# INPUT.net
KiCad netlist of a schematic drawn in Altium Designer
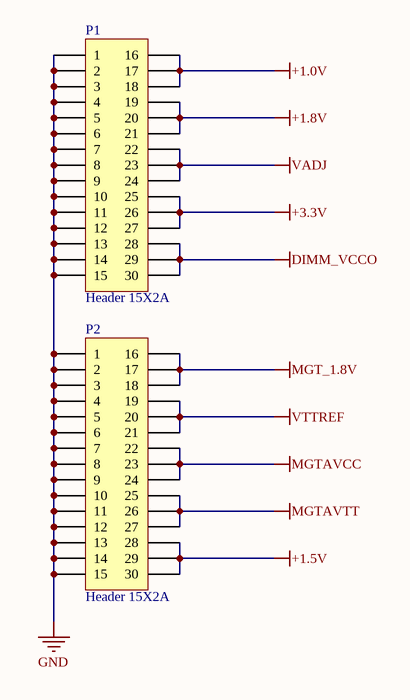
[diagram p0: INPUT.SchDoc]

(export (version "E")
  (design (tool "Eeschema 10.0.6"))
  (components
    (comp (ref "P1")
      (value "Header 15X2A")
      (footprint "HDR2X15_CEN")
      (description "Header, 15-Pin, Dual row")
      (fields (field (name "PUBLISHER") "Altium Limited"))
      (libsource (lib "Miscellaneous Connectors") (part "Header 15X2A"))
    )
    (comp (ref "P2")
      (value "Header 15X2A")
      (footprint "HDR2X15_CEN")
      (description "Header, 15-Pin, Dual row")
      (fields (field (name "PUBLISHER") "Altium Limited"))
      (libsource (lib "Miscellaneous Connectors") (part "Header 15X2A"))
    )
  )
  (nets
    (net (code "1") (name "+1.0V") (class "Default")
      (node (ref "P1") (pin "16") (pinfunction "16_16") (pintype "passive"))
      (node (ref "P1") (pin "17") (pinfunction "17_17") (pintype "passive"))
      (node (ref "P1") (pin "18") (pinfunction "18_18") (pintype "passive"))
    )
    (net (code "2") (name "+1.5V") (class "Default")
      (node (ref "P2") (pin "28") (pinfunction "28_28") (pintype "passive"))
      (node (ref "P2") (pin "29") (pinfunction "29_29") (pintype "passive"))
      (node (ref "P2") (pin "30") (pinfunction "30_30") (pintype "passive"))
    )
    (net (code "3") (name "+1.8V") (class "Default")
      (node (ref "P1") (pin "19") (pinfunction "19_19") (pintype "passive"))
      (node (ref "P1") (pin "20") (pinfunction "20_20") (pintype "passive"))
      (node (ref "P1") (pin "21") (pinfunction "21_21") (pintype "passive"))
    )
    (net (code "4") (name "+3.3V") (class "Default")
      (node (ref "P1") (pin "25") (pinfunction "25_25") (pintype "passive"))
      (node (ref "P1") (pin "26") (pinfunction "26_26") (pintype "passive"))
      (node (ref "P1") (pin "27") (pinfunction "27_27") (pintype "passive"))
    )
    (net (code "5") (name "DIMM_VCCO") (class "Default")
      (node (ref "P1") (pin "28") (pinfunction "28_28") (pintype "passive"))
      (node (ref "P1") (pin "29") (pinfunction "29_29") (pintype "passive"))
      (node (ref "P1") (pin "30") (pinfunction "30_30") (pintype "passive"))
    )
    (net (code "6") (name "GND") (class "Default")
      (node (ref "P1") (pin "1") (pinfunction "1_1") (pintype "passive"))
      (node (ref "P1") (pin "10") (pinfunction "10_10") (pintype "passive"))
      (node (ref "P1") (pin "11") (pinfunction "11_11") (pintype "passive"))
      (node (ref "P1") (pin "12") (pinfunction "12_12") (pintype "passive"))
      (node (ref "P1") (pin "13") (pinfunction "13_13") (pintype "passive"))
      (node (ref "P1") (pin "14") (pinfunction "14_14") (pintype "passive"))
      (node (ref "P1") (pin "15") (pinfunction "15_15") (pintype "passive"))
      (node (ref "P1") (pin "2") (pinfunction "2_2") (pintype "passive"))
      (node (ref "P1") (pin "3") (pinfunction "3_3") (pintype "passive"))
      (node (ref "P1") (pin "4") (pinfunction "4_4") (pintype "passive"))
      (node (ref "P1") (pin "5") (pinfunction "5_5") (pintype "passive"))
      (node (ref "P1") (pin "6") (pinfunction "6_6") (pintype "passive"))
      (node (ref "P1") (pin "7") (pinfunction "7_7") (pintype "passive"))
      (node (ref "P1") (pin "8") (pinfunction "8_8") (pintype "passive"))
      (node (ref "P1") (pin "9") (pinfunction "9_9") (pintype "passive"))
      (node (ref "P2") (pin "1") (pinfunction "1_1") (pintype "passive"))
      (node (ref "P2") (pin "10") (pinfunction "10_10") (pintype "passive"))
      (node (ref "P2") (pin "11") (pinfunction "11_11") (pintype "passive"))
      (node (ref "P2") (pin "12") (pinfunction "12_12") (pintype "passive"))
      (node (ref "P2") (pin "13") (pinfunction "13_13") (pintype "passive"))
      (node (ref "P2") (pin "14") (pinfunction "14_14") (pintype "passive"))
      (node (ref "P2") (pin "15") (pinfunction "15_15") (pintype "passive"))
      (node (ref "P2") (pin "2") (pinfunction "2_2") (pintype "passive"))
      (node (ref "P2") (pin "3") (pinfunction "3_3") (pintype "passive"))
      (node (ref "P2") (pin "4") (pinfunction "4_4") (pintype "passive"))
      (node (ref "P2") (pin "5") (pinfunction "5_5") (pintype "passive"))
      (node (ref "P2") (pin "6") (pinfunction "6_6") (pintype "passive"))
      (node (ref "P2") (pin "7") (pinfunction "7_7") (pintype "passive"))
      (node (ref "P2") (pin "8") (pinfunction "8_8") (pintype "passive"))
      (node (ref "P2") (pin "9") (pinfunction "9_9") (pintype "passive"))
    )
    (net (code "7") (name "MGTAVCC") (class "Default")
      (node (ref "P2") (pin "22") (pinfunction "22_22") (pintype "passive"))
      (node (ref "P2") (pin "23") (pinfunction "23_23") (pintype "passive"))
      (node (ref "P2") (pin "24") (pinfunction "24_24") (pintype "passive"))
    )
    (net (code "8") (name "MGTAVTT") (class "Default")
      (node (ref "P2") (pin "25") (pinfunction "25_25") (pintype "passive"))
      (node (ref "P2") (pin "26") (pinfunction "26_26") (pintype "passive"))
      (node (ref "P2") (pin "27") (pinfunction "27_27") (pintype "passive"))
    )
    (net (code "9") (name "MGT_1.8V") (class "Default")
      (node (ref "P2") (pin "16") (pinfunction "16_16") (pintype "passive"))
      (node (ref "P2") (pin "17") (pinfunction "17_17") (pintype "passive"))
      (node (ref "P2") (pin "18") (pinfunction "18_18") (pintype "passive"))
    )
    (net (code "10") (name "VADJ") (class "Default")
      (node (ref "P1") (pin "22") (pinfunction "22_22") (pintype "passive"))
      (node (ref "P1") (pin "23") (pinfunction "23_23") (pintype "passive"))
      (node (ref "P1") (pin "24") (pinfunction "24_24") (pintype "passive"))
    )
    (net (code "11") (name "VTTREF") (class "Default")
      (node (ref "P2") (pin "19") (pinfunction "19_19") (pintype "passive"))
      (node (ref "P2") (pin "20") (pinfunction "20_20") (pintype "passive"))
      (node (ref "P2") (pin "21") (pinfunction "21_21") (pintype "passive"))
    )
  )
)
